# 07_-_PERIPHERALS.net
KiCad netlist of a schematic drawn in Altium Designer
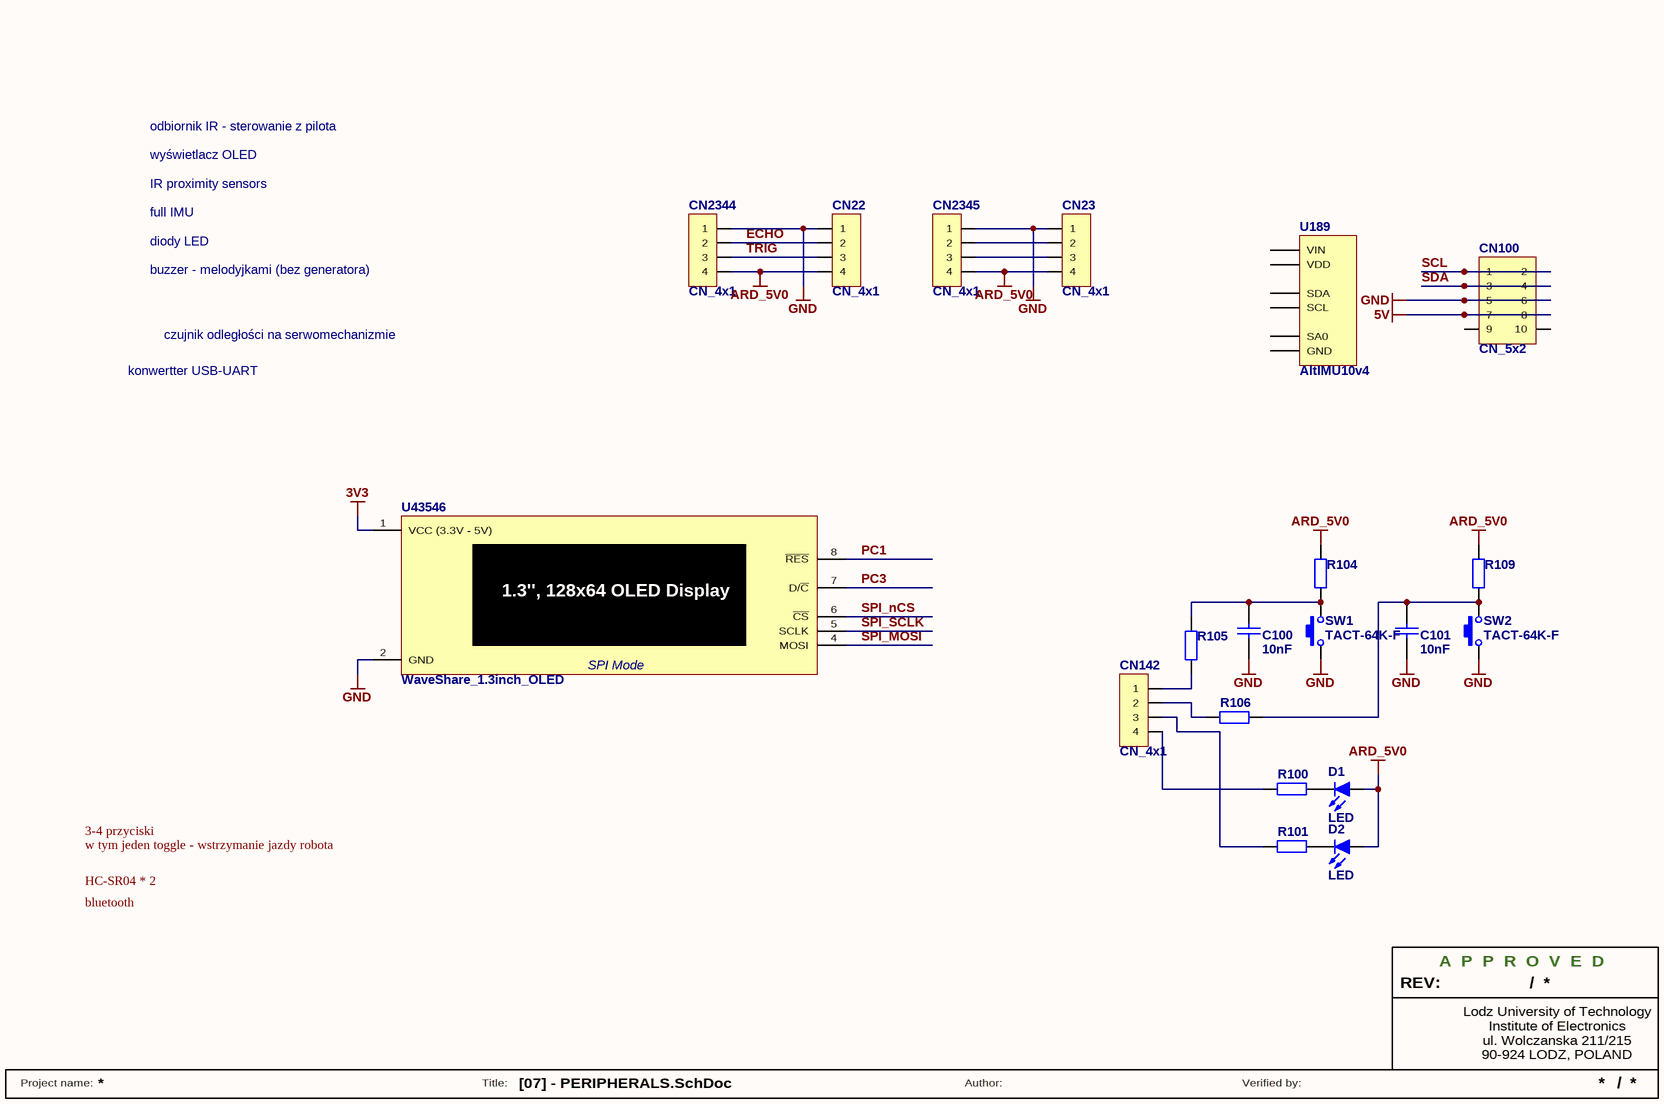
[diagram p0: [07] - PERIPHERALS.SchDoc]

(export (version "E")
  (design (tool "Eeschema 10.0.6"))
  (components
    (comp (ref "C100")
      (value "10nF")
      (footprint "C0805")
      (description "Capacitor")
      (libsource (lib "capacitors") (part "Cap"))
    )
    (comp (ref "C101")
      (value "10nF")
      (footprint "C0805")
      (description "Capacitor")
      (libsource (lib "capacitors") (part "Cap"))
    )
    (comp (ref "CN22")
      (value "CN_4x1")
      (footprint "GP_4x1H_F")
      (libsource (lib "goldpin_female") (part "CN_4x1"))
    )
    (comp (ref "CN23")
      (value "CN_4x1")
      (footprint "GP_4x1H_F")
      (libsource (lib "goldpin_female") (part "CN_4x1"))
    )
    (comp (ref "CN100")
      (value "CN_5x2")
      (footprint "GP_5x2H_F")
      (libsource (lib "goldpin_female") (part "CN_5x2"))
    )
    (comp (ref "CN142")
      (value "CN_4x1")
      (footprint "GP_4x1")
      (libsource (lib "goldpin_male") (part "CN_4x1"))
    )
    (comp (ref "CN2344")
      (value "CN_4x1")
      (footprint "GP_4x1")
      (libsource (lib "goldpin_male") (part "CN_4x1"))
    )
    (comp (ref "CN2345")
      (value "CN_4x1")
      (footprint "GP_4x1")
      (libsource (lib "goldpin_male") (part "CN_4x1"))
    )
    (comp (ref "D1")
      (value "LED")
      (footprint "LED-Polarized - 3mm")
      (description "Typical RED, GREEN, YELLOW, AMBER GaAs LED")
      (libsource (lib "leds") (part "LED"))
    )
    (comp (ref "D2")
      (value "LED")
      (footprint "LED-Polarized - 3mm")
      (description "Typical RED, GREEN, YELLOW, AMBER GaAs LED")
      (libsource (lib "leds") (part "LED"))
    )
    (comp (ref "R100")
      (value "~")
      (footprint "R0805")
      (description "Resistor")
      (libsource (lib "") (part "Res_1"))
    )
    (comp (ref "R101")
      (value "~")
      (footprint "R0805")
      (description "Resistor")
      (libsource (lib "") (part "Res_1"))
    )
    (comp (ref "R104")
      (value "~")
      (footprint "R0805")
      (description "Resistor")
      (libsource (lib "resistors") (part "Res"))
    )
    (comp (ref "R105")
      (value "~")
      (footprint "R0805")
      (description "Resistor")
      (libsource (lib "resistors") (part "Res"))
    )
    (comp (ref "R106")
      (value "~")
      (footprint "R0805")
      (description "Resistor")
      (libsource (lib "") (part "Res_1"))
    )
    (comp (ref "R109")
      (value "~")
      (footprint "R0805")
      (description "Resistor")
      (libsource (lib "resistors") (part "Res"))
    )
    (comp (ref "SW1")
      (value "TACT-64K-F")
      (footprint "TACT-64K-F")
      (description "6x6mm THT Tactile SPST-NO Switch")
      (libsource (lib "microswitches") (part "TACT-64K-F"))
    )
    (comp (ref "SW2")
      (value "TACT-64K-F")
      (footprint "TACT-64K-F")
      (description "6x6mm THT Tactile SPST-NO Switch")
      (libsource (lib "microswitches") (part "TACT-64K-F"))
    )
    (comp (ref "U189")
      (value "AltIMU10v4")
      (footprint "AltIMU-10 v4")
      (description "Pololu Gyro, Accelerometer, Compass, and Altimeter (L3GD20H, LSM303D, and LPS25H Carrier)")
      (libsource (lib "mems_and_imu_modules") (part "AltIMU10v4"))
    )
    (comp (ref "U43546")
      (value "WaveShare_1.3inch_OLED")
      (footprint "WaveShare_1.3INCH_OLED")
      (description "DEP096032B-W OLED Display")
      (libsource (lib "oled_displays") (part "WaveShare_1.3inch_OLED"))
    )
  )
  (nets
    (net (code "2") (name "/ECHO") (class "Default")
      (node (ref "CN22") (pin "2") (pinfunction "2_2") (pintype "passive"))
      (node (ref "CN2344") (pin "2") (pinfunction "2_2") (pintype "passive"))
    )
    (net (code "4") (name "/PC1") (class "Default")
      (node (ref "U43546") (pin "8") (pinfunction "~{RES}_8") (pintype "passive"))
    )
    (net (code "5") (name "/PC3") (class "Default")
      (node (ref "U43546") (pin "7") (pinfunction "D/~{C}_7") (pintype "passive"))
    )
    (net (code "6") (name "/SCL") (class "Default")
      (node (ref "CN100") (pin "1") (pinfunction "1_1") (pintype "passive"))
      (node (ref "CN100") (pin "2") (pinfunction "2_2") (pintype "passive"))
    )
    (net (code "7") (name "/SDA") (class "Default")
      (node (ref "CN100") (pin "3") (pinfunction "3_3") (pintype "passive"))
      (node (ref "CN100") (pin "4") (pinfunction "4_4") (pintype "passive"))
    )
    (net (code "8") (name "/SPI_MOSI") (class "Default")
      (node (ref "U43546") (pin "4") (pinfunction "MOSI_4") (pintype "passive"))
    )
    (net (code "9") (name "/SPI_SCLK") (class "Default")
      (node (ref "U43546") (pin "5") (pinfunction "SCLK_5") (pintype "passive"))
    )
    (net (code "10") (name "/SPI_nCS") (class "Default")
      (node (ref "U43546") (pin "6") (pinfunction "~{CS}_6") (pintype "passive"))
    )
    (net (code "11") (name "/TRIG") (class "Default")
      (node (ref "CN22") (pin "3") (pinfunction "3_3") (pintype "passive"))
      (node (ref "CN2344") (pin "3") (pinfunction "3_3") (pintype "passive"))
    )
    (net (code "14") (name "3V3") (class "Default")
      (node (ref "U43546") (pin "1") (pinfunction "VCC_(3.3V_-_5V)_1") (pintype "passive"))
    )
    (net (code "15") (name "5V") (class "Default")
      (node (ref "CN100") (pin "7") (pinfunction "7_7") (pintype "passive"))
      (node (ref "CN100") (pin "8") (pinfunction "8_8") (pintype "passive"))
    )
    (net (code "16") (name "ARD_5V0") (class "Default")
      (node (ref "CN22") (pin "4") (pinfunction "4_4") (pintype "passive"))
      (node (ref "CN23") (pin "4") (pinfunction "4_4") (pintype "passive"))
      (node (ref "CN2344") (pin "4") (pinfunction "4_4") (pintype "passive"))
      (node (ref "CN2345") (pin "4") (pinfunction "4_4") (pintype "passive"))
      (node (ref "D1") (pin "1") (pinfunction "A_1") (pintype "passive"))
      (node (ref "D2") (pin "1") (pinfunction "A_1") (pintype "passive"))
      (node (ref "R104") (pin "2") (pinfunction "2_2") (pintype "passive"))
      (node (ref "R109") (pin "2") (pinfunction "2_2") (pintype "passive"))
    )
    (net (code "17") (name "GND") (class "Default")
      (node (ref "C100") (pin "1") (pinfunction "1_1") (pintype "passive"))
      (node (ref "C101") (pin "1") (pinfunction "1_1") (pintype "passive"))
      (node (ref "CN100") (pin "5") (pinfunction "5_5") (pintype "passive"))
      (node (ref "CN100") (pin "6") (pinfunction "6_6") (pintype "passive"))
      (node (ref "CN22") (pin "1") (pinfunction "1_1") (pintype "passive"))
      (node (ref "CN23") (pin "1") (pinfunction "1_1") (pintype "passive"))
      (node (ref "CN2344") (pin "1") (pinfunction "1_1") (pintype "passive"))
      (node (ref "CN2345") (pin "1") (pinfunction "1_1") (pintype "passive"))
      (node (ref "SW1") (pin "1") (pinfunction "1_1") (pintype "passive"))
      (node (ref "SW2") (pin "1") (pinfunction "1_1") (pintype "passive"))
      (node (ref "U43546") (pin "2") (pinfunction "GND_2") (pintype "passive"))
    )
    (net (code "18") (name "Net-(C100-Pad2)") (class "Default")
      (node (ref "C100") (pin "2") (pinfunction "2_2") (pintype "passive"))
      (node (ref "R104") (pin "1") (pinfunction "1_1") (pintype "passive"))
      (node (ref "R105") (pin "2") (pinfunction "2_2") (pintype "passive"))
      (node (ref "SW1") (pin "2") (pinfunction "2_2") (pintype "passive"))
    )
    (net (code "19") (name "Net-(C101-Pad2)") (class "Default")
      (node (ref "C101") (pin "2") (pinfunction "2_2") (pintype "passive"))
      (node (ref "R106") (pin "2") (pinfunction "2_2") (pintype "passive"))
      (node (ref "R109") (pin "1") (pinfunction "1_1") (pintype "passive"))
      (node (ref "SW2") (pin "2") (pinfunction "2_2") (pintype "passive"))
    )
    (net (code "20") (name "Net-(CN23-Pad2)") (class "Default")
      (node (ref "CN23") (pin "2") (pinfunction "2_2") (pintype "passive"))
      (node (ref "CN2345") (pin "2") (pinfunction "2_2") (pintype "passive"))
    )
    (net (code "21") (name "Net-(CN23-Pad3)") (class "Default")
      (node (ref "CN23") (pin "3") (pinfunction "3_3") (pintype "passive"))
      (node (ref "CN2345") (pin "3") (pinfunction "3_3") (pintype "passive"))
    )
    (net (code "22") (name "Net-(CN142-Pad1)") (class "Default")
      (node (ref "CN142") (pin "1") (pinfunction "1_1") (pintype "passive"))
      (node (ref "R105") (pin "1") (pinfunction "1_1") (pintype "passive"))
    )
    (net (code "23") (name "Net-(CN142-Pad2)") (class "Default")
      (node (ref "CN142") (pin "2") (pinfunction "2_2") (pintype "passive"))
      (node (ref "R106") (pin "1") (pinfunction "1_1") (pintype "passive"))
    )
    (net (code "24") (name "Net-(CN142-Pad3)") (class "Default")
      (node (ref "CN142") (pin "3") (pinfunction "3_3") (pintype "passive"))
      (node (ref "R101") (pin "1") (pinfunction "1_1") (pintype "passive"))
    )
    (net (code "25") (name "Net-(CN142-Pad4)") (class "Default")
      (node (ref "CN142") (pin "4") (pinfunction "4_4") (pintype "passive"))
      (node (ref "R100") (pin "1") (pinfunction "1_1") (pintype "passive"))
    )
    (net (code "26") (name "Net-(D1-K)") (class "Default")
      (node (ref "D1") (pin "2") (pinfunction "K_2") (pintype "passive"))
      (node (ref "R100") (pin "2") (pinfunction "2_2") (pintype "passive"))
    )
    (net (code "27") (name "Net-(D2-K)") (class "Default")
      (node (ref "D2") (pin "2") (pinfunction "K_2") (pintype "passive"))
      (node (ref "R101") (pin "2") (pinfunction "2_2") (pintype "passive"))
    )
    (net (code "28") (name "unconnected-(CN100-Pad9)") (class "Default")
      (node (ref "CN100") (pin "9") (pinfunction "9_9") (pintype "passive"))
    )
    (net (code "29") (name "unconnected-(CN100-Pad10)") (class "Default")
      (node (ref "CN100") (pin "10") (pinfunction "10_10") (pintype "passive"))
    )
    (net (code "30") (name "unconnected-(U189-GND-Pad1)") (class "Default")
      (node (ref "U189") (pin "1") (pinfunction "GND_1") (pintype "passive"))
    )
    (net (code "31") (name "unconnected-(U189-SA0-Pad2)") (class "Default")
      (node (ref "U189") (pin "2") (pinfunction "SA0_2") (pintype "passive"))
    )
    (net (code "32") (name "unconnected-(U189-SCL-Pad6)") (class "Default")
      (node (ref "U189") (pin "6") (pinfunction "SCL_6") (pintype "passive"))
    )
    (net (code "33") (name "unconnected-(U189-SDA-Pad5)") (class "Default")
      (node (ref "U189") (pin "5") (pinfunction "SDA_5") (pintype "passive"))
    )
    (net (code "34") (name "unconnected-(U189-VDD-Pad4)") (class "Default")
      (node (ref "U189") (pin "4") (pinfunction "VDD_4") (pintype "passive"))
    )
    (net (code "35") (name "unconnected-(U189-VIN-Pad3)") (class "Default")
      (node (ref "U189") (pin "3") (pinfunction "VIN_3") (pintype "passive"))
    )
    (net (code "36") (name "unconnected-(U43546-NC_{slash}_SDAOUT-Pad7)") (class "Default")
      (node (ref "U43546") (pin "7") (pinfunction "NC_/_SDAOUT_7") (pintype "passive"))
    )
  )
)
